# schematic.net
KiCad netlist of a schematic drawn in EAGLE
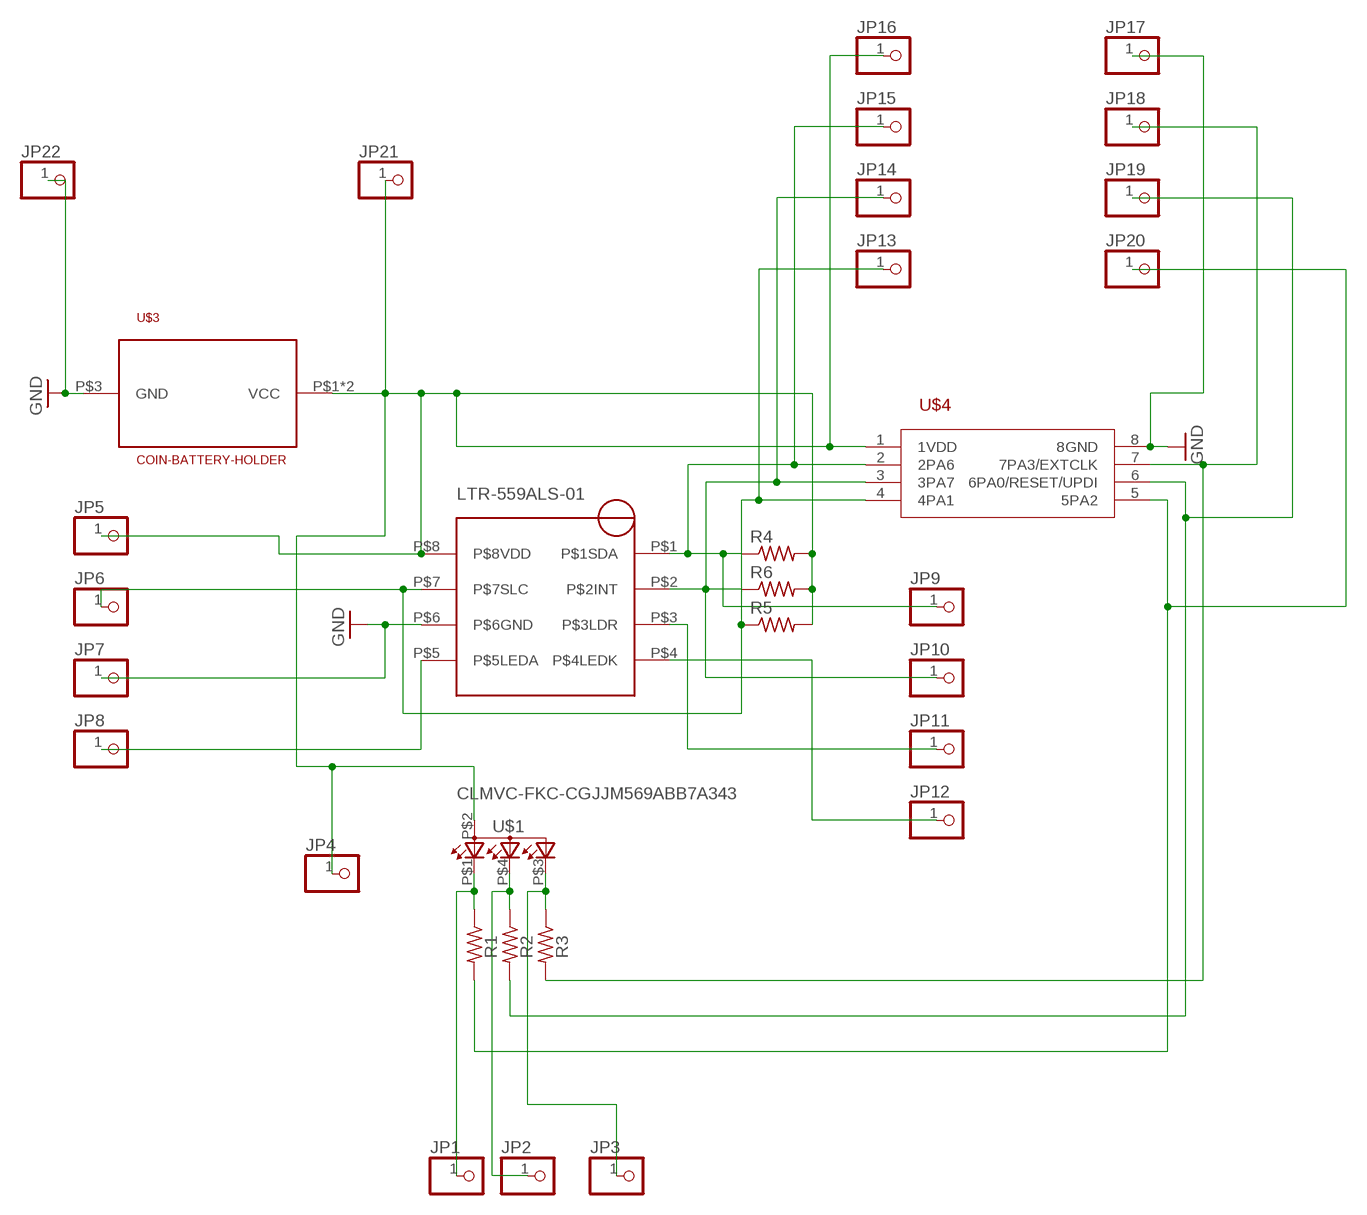
[diagram p0: schematic, sheet 1]

(export (version "E")
  (design (tool "Eeschema 10.0.6"))
  (components
    (comp (ref "JP1")
      (value "PINHD-1X1")
      (footprint "eagle-import:1X01")
      (libsource (lib "eagle-import") (part "PINHD-1X1"))
    )
    (comp (ref "JP2")
      (value "PINHD-1X1")
      (footprint "eagle-import:1X01")
      (libsource (lib "eagle-import") (part "PINHD-1X1"))
    )
    (comp (ref "JP3")
      (value "PINHD-1X1")
      (footprint "eagle-import:1X01")
      (libsource (lib "eagle-import") (part "PINHD-1X1"))
    )
    (comp (ref "JP4")
      (value "PINHD-1X1")
      (footprint "eagle-import:1X01")
      (libsource (lib "eagle-import") (part "PINHD-1X1"))
    )
    (comp (ref "JP5")
      (value "PINHD-1X1")
      (footprint "eagle-import:1X01")
      (libsource (lib "eagle-import") (part "PINHD-1X1"))
    )
    (comp (ref "JP6")
      (value "PINHD-1X1")
      (footprint "eagle-import:1X01")
      (libsource (lib "eagle-import") (part "PINHD-1X1"))
    )
    (comp (ref "JP7")
      (value "PINHD-1X1")
      (footprint "eagle-import:1X01")
      (libsource (lib "eagle-import") (part "PINHD-1X1"))
    )
    (comp (ref "JP8")
      (value "PINHD-1X1")
      (footprint "eagle-import:1X01")
      (libsource (lib "eagle-import") (part "PINHD-1X1"))
    )
    (comp (ref "JP9")
      (value "PINHD-1X1")
      (footprint "eagle-import:1X01")
      (libsource (lib "eagle-import") (part "PINHD-1X1"))
    )
    (comp (ref "JP10")
      (value "PINHD-1X1")
      (footprint "eagle-import:1X01")
      (libsource (lib "eagle-import") (part "PINHD-1X1"))
    )
    (comp (ref "JP11")
      (value "PINHD-1X1")
      (footprint "eagle-import:1X01")
      (libsource (lib "eagle-import") (part "PINHD-1X1"))
    )
    (comp (ref "JP12")
      (value "PINHD-1X1")
      (footprint "eagle-import:1X01")
      (libsource (lib "eagle-import") (part "PINHD-1X1"))
    )
    (comp (ref "JP13")
      (value "PINHD-1X1")
      (footprint "eagle-import:1X01")
      (libsource (lib "eagle-import") (part "PINHD-1X1"))
    )
    (comp (ref "JP14")
      (value "PINHD-1X1")
      (footprint "eagle-import:1X01")
      (libsource (lib "eagle-import") (part "PINHD-1X1"))
    )
    (comp (ref "JP15")
      (value "PINHD-1X1")
      (footprint "eagle-import:1X01")
      (libsource (lib "eagle-import") (part "PINHD-1X1"))
    )
    (comp (ref "JP16")
      (value "PINHD-1X1")
      (footprint "eagle-import:1X01")
      (libsource (lib "eagle-import") (part "PINHD-1X1"))
    )
    (comp (ref "JP17")
      (value "PINHD-1X1")
      (footprint "eagle-import:1X01")
      (libsource (lib "eagle-import") (part "PINHD-1X1"))
    )
    (comp (ref "JP18")
      (value "PINHD-1X1")
      (footprint "eagle-import:1X01")
      (libsource (lib "eagle-import") (part "PINHD-1X1"))
    )
    (comp (ref "JP19")
      (value "PINHD-1X1")
      (footprint "eagle-import:1X01")
      (libsource (lib "eagle-import") (part "PINHD-1X1"))
    )
    (comp (ref "JP20")
      (value "PINHD-1X1")
      (footprint "eagle-import:1X01")
      (libsource (lib "eagle-import") (part "PINHD-1X1"))
    )
    (comp (ref "JP21")
      (value "PINHD-1X1")
      (footprint "eagle-import:1X01")
      (libsource (lib "eagle-import") (part "PINHD-1X1"))
    )
    (comp (ref "JP22")
      (value "PINHD-1X1")
      (footprint "eagle-import:1X01")
      (libsource (lib "eagle-import") (part "PINHD-1X1"))
    )
    (comp (ref "R1")
      (value "R-US_R0805")
      (footprint "eagle-import:R0805")
      (libsource (lib "eagle-import") (part "R-US_R0805"))
    )
    (comp (ref "R2")
      (value "R-US_R0805")
      (footprint "eagle-import:R0805")
      (libsource (lib "eagle-import") (part "R-US_R0805"))
    )
    (comp (ref "R3")
      (value "R-US_R0805")
      (footprint "eagle-import:R0805")
      (libsource (lib "eagle-import") (part "R-US_R0805"))
    )
    (comp (ref "R4")
      (value "R-US_R0805")
      (footprint "eagle-import:R0805")
      (libsource (lib "eagle-import") (part "R-US_R0805"))
    )
    (comp (ref "R5")
      (value "R-US_R0805")
      (footprint "eagle-import:R0805")
      (libsource (lib "eagle-import") (part "R-US_R0805"))
    )
    (comp (ref "R6")
      (value "R-US_R0805")
      (footprint "eagle-import:R0805")
      (libsource (lib "eagle-import") (part "R-US_R0805"))
    )
    (comp (ref "U$1")
      (value "CLMVC-FKC-CGJJM569ABB7A343")
      (footprint "eagle-import:CLMVC-FKC-CGJJM569ABB7A343")
      (libsource (lib "eagle-import") (part "CLMVC-FKC-CGJJM569ABB7A343"))
    )
    (comp (ref "U$2")
      (value "LTR-559ALS-01")
      (footprint "eagle-import:LTR-559ALS-01")
      (libsource (lib "eagle-import") (part "LTR-559ALS-01"))
    )
    (comp (ref "U$3")
      (value "COIN-BATTERY-HOLDER")
      (footprint "eagle-import:3034_C")
      (libsource (lib "eagle-import") (part "COIN-BATTERY-HOLDER"))
    )
    (comp (ref "U$4")
      (value "ATTINY402-SSNR")
      (footprint "eagle-import:SOIC127P600X175-8N")
      (libsource (lib "eagle-import") (part "ATTINY402-SSNR"))
    )
  )
  (nets
    (net (code "1") (name "GND") (class "Default")
      (node (ref "JP17") (pin "1") (pinfunction "1_1") (pintype "passive"))
      (node (ref "JP22") (pin "1") (pinfunction "1_1") (pintype "passive"))
      (node (ref "JP7") (pin "1") (pinfunction "1_1") (pintype "passive"))
      (node (ref "U$2") (pin "P$6") (pinfunction "P$6GND_P$6") (pintype "bidirectional"))
      (node (ref "U$3") (pin "P$3") (pinfunction "GND_P$3") (pintype "bidirectional"))
      (node (ref "U$4") (pin "8") (pinfunction "8GND_8") (pintype "bidirectional"))
    )
    (net (code "2") (name "Net-(U$1-CBLUE)") (class "Default")
      (node (ref "JP2") (pin "1") (pinfunction "1_1") (pintype "passive"))
      (node (ref "R2") (pin "1") (pinfunction "1_1") (pintype "passive"))
      (node (ref "U$1") (pin "P$4") (pinfunction "CBLUE_P$4") (pintype "passive"))
    )
    (net (code "3") (name "Net-(U$1-CGREEN)") (class "Default")
      (node (ref "JP3") (pin "1") (pinfunction "1_1") (pintype "passive"))
      (node (ref "R3") (pin "1") (pinfunction "1_1") (pintype "passive"))
      (node (ref "U$1") (pin "P$3") (pinfunction "CGREEN_P$3") (pintype "passive"))
    )
    (net (code "4") (name "Net-(U$1-CRED)") (class "Default")
      (node (ref "JP1") (pin "1") (pinfunction "1_1") (pintype "passive"))
      (node (ref "R1") (pin "1") (pinfunction "1_1") (pintype "passive"))
      (node (ref "U$1") (pin "P$1") (pinfunction "CRED_P$1") (pintype "passive"))
    )
    (net (code "5") (name "Net-(U$1-GND)") (class "Default")
      (node (ref "JP16") (pin "1") (pinfunction "1_1") (pintype "passive"))
      (node (ref "JP21") (pin "1") (pinfunction "1_1") (pintype "passive"))
      (node (ref "JP4") (pin "1") (pinfunction "1_1") (pintype "passive"))
      (node (ref "JP5") (pin "1") (pinfunction "1_1") (pintype "passive"))
      (node (ref "R4") (pin "2") (pinfunction "2_2") (pintype "passive"))
      (node (ref "R5") (pin "2") (pinfunction "2_2") (pintype "passive"))
      (node (ref "R6") (pin "2") (pinfunction "2_2") (pintype "passive"))
      (node (ref "U$1") (pin "P$2") (pinfunction "GND_P$2") (pintype "passive"))
      (node (ref "U$2") (pin "P$8") (pinfunction "P$8VDD_P$8") (pintype "bidirectional"))
      (node (ref "U$3") (pin "P$1") (pinfunction "VCC_P$1") (pintype "bidirectional"))
      (node (ref "U$3") (pin "P$2") (pinfunction "VCC_P$2") (pintype "bidirectional"))
      (node (ref "U$4") (pin "1") (pinfunction "1VDD_1") (pintype "bidirectional"))
    )
    (net (code "6") (name "Net-(U$2-P$1SDA)") (class "Default")
      (node (ref "JP15") (pin "1") (pinfunction "1_1") (pintype "passive"))
      (node (ref "JP9") (pin "1") (pinfunction "1_1") (pintype "passive"))
      (node (ref "R4") (pin "1") (pinfunction "1_1") (pintype "passive"))
      (node (ref "U$2") (pin "P$1") (pinfunction "P$1SDA_P$1") (pintype "bidirectional"))
      (node (ref "U$4") (pin "2") (pinfunction "2PA6_2") (pintype "bidirectional"))
    )
    (net (code "7") (name "Net-(U$2-P$2INT)") (class "Default")
      (node (ref "JP10") (pin "1") (pinfunction "1_1") (pintype "passive"))
      (node (ref "JP14") (pin "1") (pinfunction "1_1") (pintype "passive"))
      (node (ref "R6") (pin "1") (pinfunction "1_1") (pintype "passive"))
      (node (ref "U$2") (pin "P$2") (pinfunction "P$2INT_P$2") (pintype "bidirectional"))
      (node (ref "U$4") (pin "3") (pinfunction "3PA7_3") (pintype "bidirectional"))
    )
    (net (code "8") (name "Net-(U$2-P$3LDR)") (class "Default")
      (node (ref "JP11") (pin "1") (pinfunction "1_1") (pintype "passive"))
      (node (ref "U$2") (pin "P$3") (pinfunction "P$3LDR_P$3") (pintype "bidirectional"))
    )
    (net (code "9") (name "Net-(U$2-P$4LEDK)") (class "Default")
      (node (ref "JP12") (pin "1") (pinfunction "1_1") (pintype "passive"))
      (node (ref "U$2") (pin "P$4") (pinfunction "P$4LEDK_P$4") (pintype "bidirectional"))
    )
    (net (code "10") (name "Net-(U$2-P$5LEDA)") (class "Default")
      (node (ref "JP8") (pin "1") (pinfunction "1_1") (pintype "passive"))
      (node (ref "U$2") (pin "P$5") (pinfunction "P$5LEDA_P$5") (pintype "bidirectional"))
    )
    (net (code "11") (name "Net-(U$2-P$7SLC)") (class "Default")
      (node (ref "JP13") (pin "1") (pinfunction "1_1") (pintype "passive"))
      (node (ref "JP6") (pin "1") (pinfunction "1_1") (pintype "passive"))
      (node (ref "R5") (pin "1") (pinfunction "1_1") (pintype "passive"))
      (node (ref "U$2") (pin "P$7") (pinfunction "P$7SLC_P$7") (pintype "bidirectional"))
      (node (ref "U$4") (pin "4") (pinfunction "4PA1_4") (pintype "bidirectional"))
    )
    (net (code "12") (name "Net-(U$4-5PA2)") (class "Default")
      (node (ref "JP20") (pin "1") (pinfunction "1_1") (pintype "passive"))
      (node (ref "R1") (pin "2") (pinfunction "2_2") (pintype "passive"))
      (node (ref "U$4") (pin "5") (pinfunction "5PA2_5") (pintype "bidirectional"))
    )
    (net (code "13") (name "Net-(U$4-6PA0{slash}RESET{slash}UPDI)") (class "Default")
      (node (ref "JP19") (pin "1") (pinfunction "1_1") (pintype "passive"))
      (node (ref "R2") (pin "2") (pinfunction "2_2") (pintype "passive"))
      (node (ref "U$4") (pin "6") (pinfunction "6PA0/RESET/UPDI_6") (pintype "bidirectional"))
    )
    (net (code "14") (name "Net-(U$4-7PA3{slash}EXTCLK)") (class "Default")
      (node (ref "JP18") (pin "1") (pinfunction "1_1") (pintype "passive"))
      (node (ref "R3") (pin "2") (pinfunction "2_2") (pintype "passive"))
      (node (ref "U$4") (pin "7") (pinfunction "7PA3/EXTCLK_7") (pintype "bidirectional"))
    )
  )
)
